# Node_Sensor_Schematic.net
KiCad netlist of a schematic drawn in Altium Designer
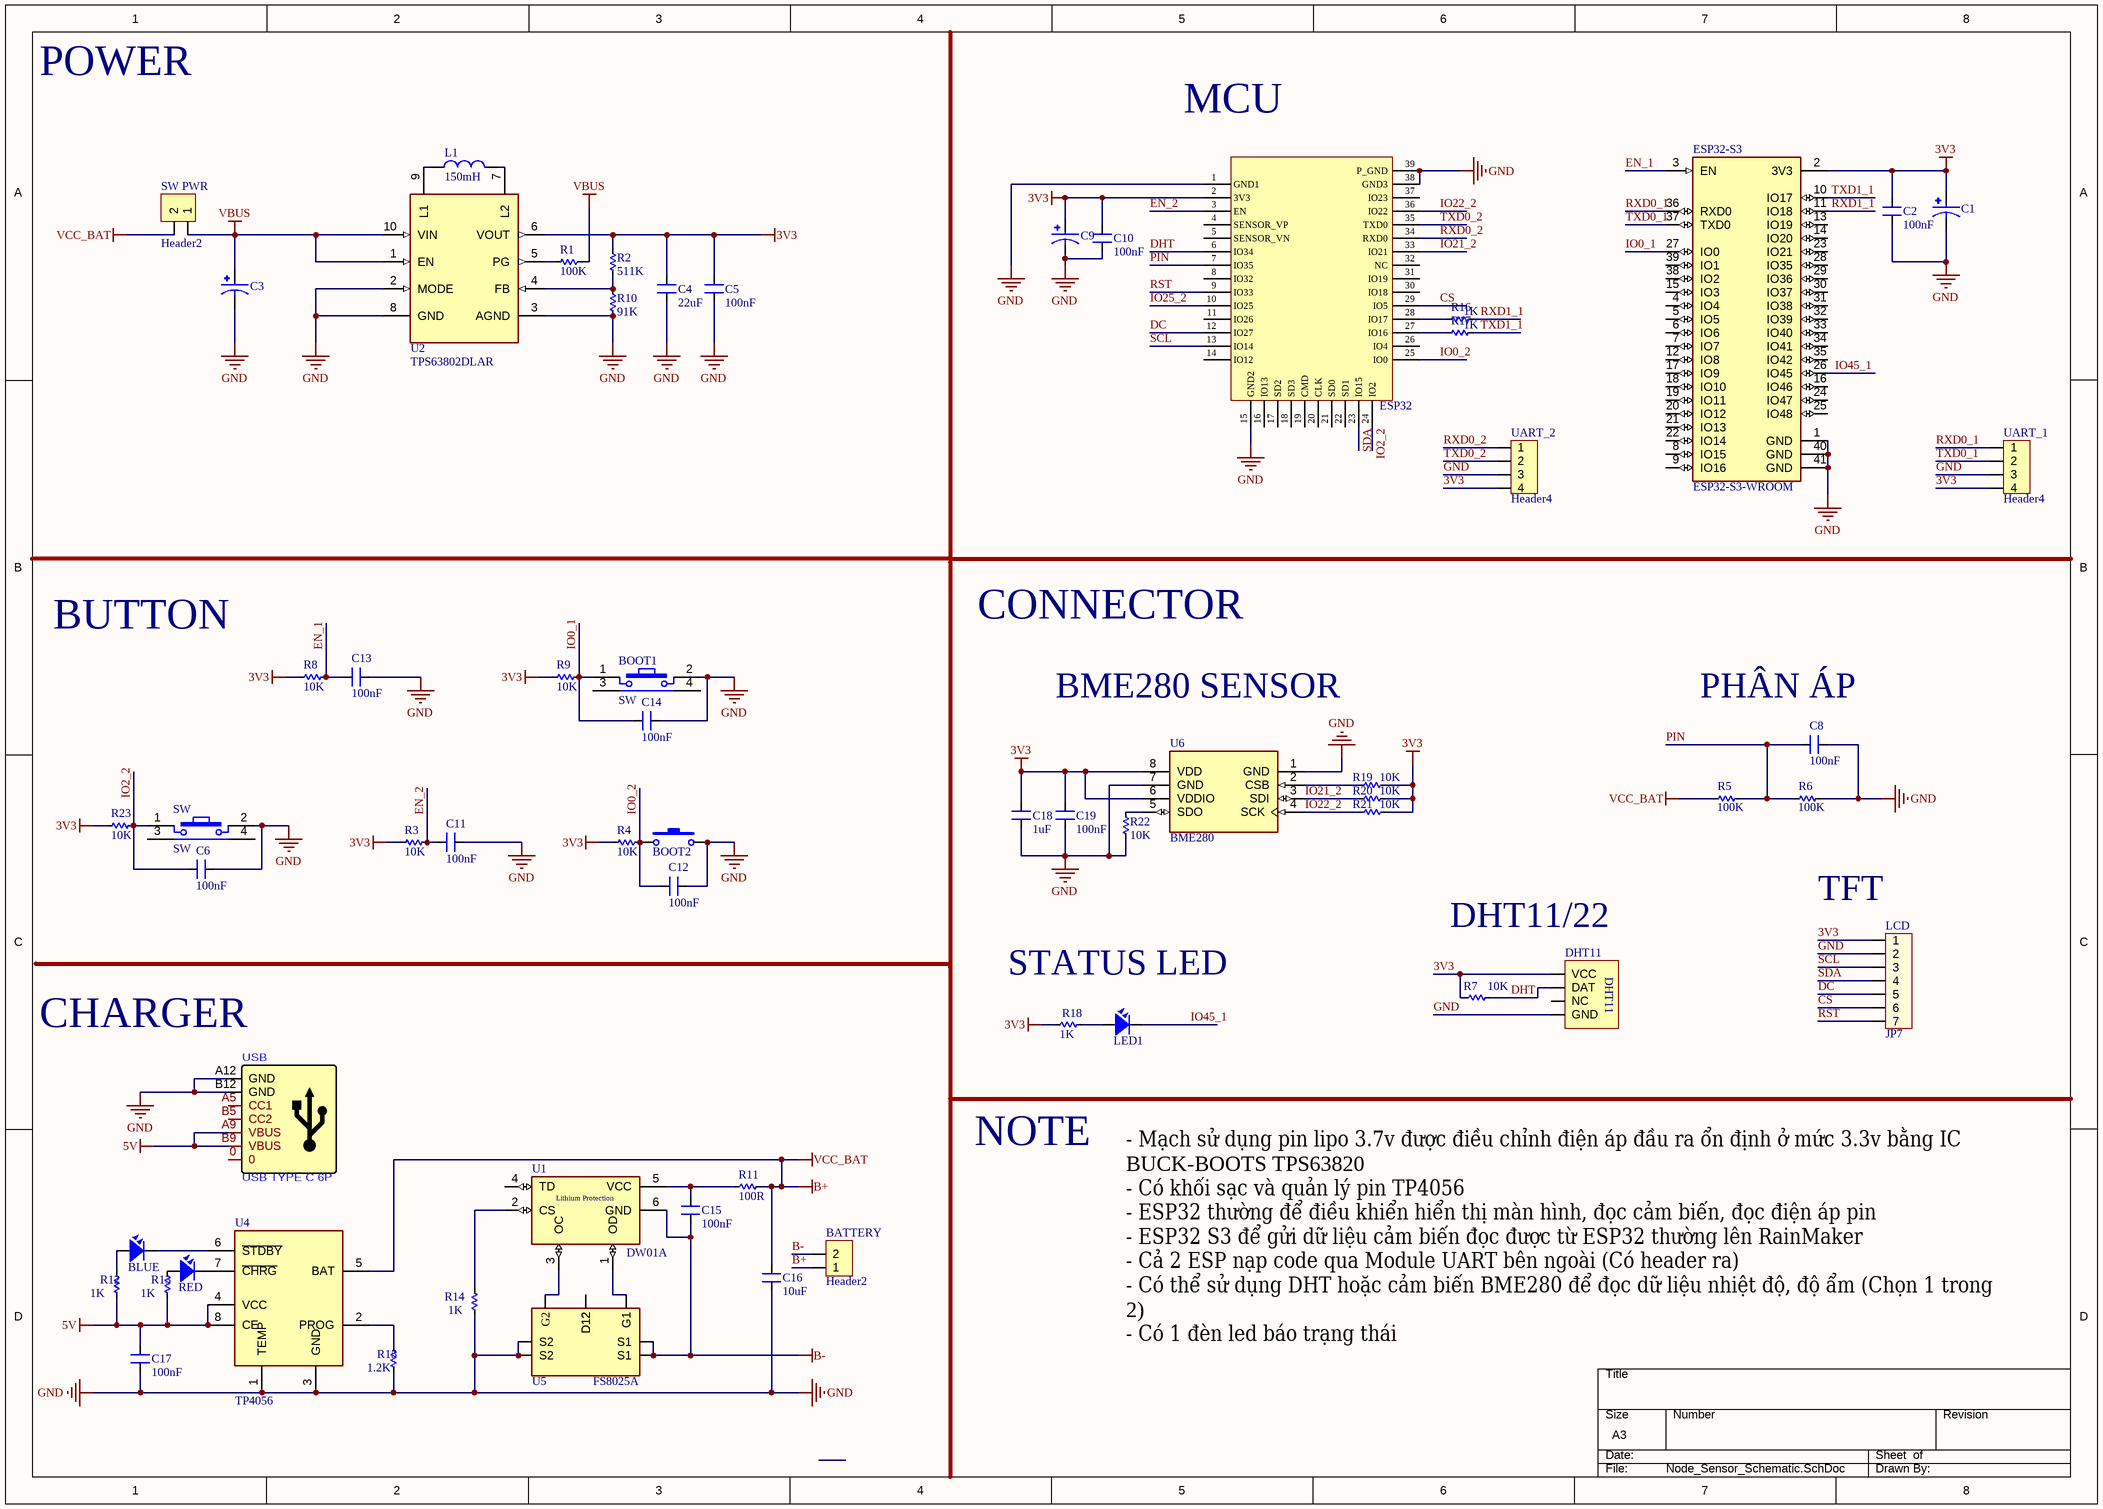
[diagram p0: Node_Sensor_Schematic.SchDoc]

(export (version "E")
  (design (tool "Eeschema 10.0.6"))
  (components
    (comp (ref "BATTERY")
      (value "Header2")
      (footprint "Header2")
      (description "Header IDC, 2 x 1 Pin Vertical 2.54mm Pitch (Non-Boxed, Male)")
      (fields
        (field (name "MANUFACTURER") "Würth Elektronik eiSos GmbH")
        (field (name "PARTNO") "613002143121")
        (field (name "CREATED BY") "Karrer Zheng")
      )
      (libsource (lib "My Library") (part "Header2"))
    )
    (comp (ref "BLUE")
      (value "LED")
      (footprint "My Library:LED-0603")
      (libsource (lib "My Library") (part "LED SMD"))
    )
    (comp (ref "BOOT1")
      (value "SW")
      (footprint "TACTILE SWITCH TC-0203")
      (description "Switch button 4 pin")
      (libsource (lib "Altium_Devzone") (part "SW4-DIP"))
    )
    (comp (ref "BOOT2")
      (value "SW-SMD")
      (footprint "SW_B3U-1000P")
      (description "Switch")
      (fields (field (name "PUBLISHER") "Altium Limited"))
      (libsource (lib "My Library") (part "SW-SMD"))
    )
    (comp (ref "C1")
      (value "CAP_TANTALUM_SMD")
      (footprint "CAP_TANTALUM_3216")
      (description "Capacitor, Tantalum")
      (fields (field (name "MF") "AVX") (field (name "MP") "TAJB475K025RNJ"))
      (libsource (lib "My Library") (part "CAP_TANTALUM_SMD"))
    )
    (comp (ref "C2")
      (value "100nF")
      (footprint "C-0603")
      (description "Cap SMD")
      (libsource (lib "My Library") (part "CM"))
    )
    (comp (ref "C3")
      (value "10uF/16V")
      (footprint "CAP_TANTALUM_3216")
      (description "Capacitor, Tantalum")
      (fields (field (name "MF") "AVX") (field (name "MP") "TAJB475K025RNJ"))
      (libsource (lib "My Library") (part "CAP_TANTALUM_SMD"))
    )
    (comp (ref "C4")
      (value "22uF")
      (footprint "SM-0805")
      (description "Cap SMD")
      (libsource (lib "My Library") (part "CM"))
    )
    (comp (ref "C5")
      (value "100nF")
      (footprint "SM-0805")
      (description "Cap SMD")
      (libsource (lib "My Library") (part "CM"))
    )
    (comp (ref "C6")
      (value "100nF")
      (footprint "C-0603")
      (description "Cap SMD")
      (libsource (lib "My Library") (part "CM"))
    )
    (comp (ref "C8")
      (value "100nF")
      (footprint "C-0603")
      (description "Cap SMD")
      (libsource (lib "My Library") (part "CM"))
    )
    (comp (ref "C9")
      (value "CAP_TANTALUM_SMD")
      (footprint "CAP_TANTALUM_3216")
      (description "Capacitor, Tantalum")
      (fields (field (name "MF") "AVX") (field (name "MP") "TAJB475K025RNJ"))
      (libsource (lib "My Library") (part "CAP_TANTALUM_SMD"))
    )
    (comp (ref "C10")
      (value "100nF")
      (footprint "C-0603")
      (description "Cap SMD")
      (libsource (lib "My Library") (part "CM"))
    )
    (comp (ref "C11")
      (value "100nF")
      (footprint "C-0603")
      (description "Cap SMD")
      (libsource (lib "My Library") (part "CM"))
    )
    (comp (ref "C12")
      (value "100nF")
      (footprint "C-0603")
      (description "Cap SMD")
      (libsource (lib "My Library") (part "CM"))
    )
    (comp (ref "C13")
      (value "100nF")
      (footprint "C-0603")
      (description "Cap SMD")
      (libsource (lib "My Library") (part "CM"))
    )
    (comp (ref "C14")
      (value "100nF")
      (footprint "C-0603")
      (description "Cap SMD")
      (libsource (lib "My Library") (part "CM"))
    )
    (comp (ref "C15")
      (value "100nF")
      (footprint "C-0603")
      (description "Cap SMD")
      (libsource (lib "My Library") (part "CM"))
    )
    (comp (ref "C16")
      (value "10uF")
      (footprint "SM-0805")
      (description "Cap SMD")
      (libsource (lib "My Library") (part "CM"))
    )
    (comp (ref "C17")
      (value "100nF")
      (footprint "C-0603")
      (description "Cap SMD")
      (libsource (lib "My Library") (part "CM"))
    )
    (comp (ref "C18")
      (value "1uF")
      (footprint "C-0603")
      (description "Cap SMD")
      (libsource (lib "My Library") (part "CM"))
    )
    (comp (ref "C19")
      (value "100nF")
      (footprint "C-0603")
      (description "Cap SMD")
      (libsource (lib "My Library") (part "CM"))
    )
    (comp (ref "DHT11")
      (value "DHT11")
      (footprint "DHT11")
      (fields
        (field (name "MANUFACTURER") "Würth Elektronik eiSos GmbH")
        (field (name "PARTNO") "613004143121")
        (field (name "CREATED BY") "Karrer Zheng")
      )
      (libsource (lib "My Library") (part "DHT11"))
    )
    (comp (ref "ESP32")
      (value "ESP32")
      (footprint "ESP32-WROOM-32U")
      (libsource (lib "My Library") (part "ESP-WROOM-32"))
    )
    (comp (ref "ESP32-S3")
      (value "ESP32-S3-WROOM")
      (footprint "ESP32-S3-WROOM-1")
      (fields
        (field (name "MF") "{'manufacturer': u'Espressif Systems'}")
        (field (name "MP") "ESP32-S3-WROOM-1-N8")
      )
      (libsource (lib "My Library") (part "ESP32-S3-WROOM"))
    )
    (comp (ref "L1")
      (value "150mH")
      (footprint "INDUCTOR_SMD_4X4MM")
      (description "Inductor")
      (libsource (lib "My Library") (part "Inductor_SMD"))
    )
    (comp (ref "LCD")
      (value "JP7")
      (footprint "653007114822")
      (description "Connector 7")
      (libsource (lib "Altium_Devzone") (part "Header7"))
    )
    (comp (ref "LED1")
      (value "LED")
      (footprint "My Library:LED-0603")
      (libsource (lib "My Library") (part "LED SMD"))
    )
    (comp (ref "R1")
      (value "100K")
      (footprint "RES-SMD-0603")
      (description "Resistor")
      (fields
        (field (name "MANUFACTURER") "Generic Components")
        (field (name "PUBLISHER") "Altium Hobart Technology Centre")
      )
      (libsource (lib "My Library") (part "Res-SMD"))
    )
    (comp (ref "R2")
      (value "511K")
      (footprint "RES-SMD-0603")
      (description "Resistor")
      (fields
        (field (name "MANUFACTURER") "Generic Components")
        (field (name "PUBLISHER") "Altium Hobart Technology Centre")
      )
      (libsource (lib "My Library") (part "Res-SMD"))
    )
    (comp (ref "R3")
      (value "10K")
      (footprint "RES-SMD-0603")
      (description "Resistor")
      (fields
        (field (name "MANUFACTURER") "Generic Components")
        (field (name "PUBLISHER") "Altium Hobart Technology Centre")
      )
      (libsource (lib "My Library") (part "Res-SMD"))
    )
    (comp (ref "R4")
      (value "10K")
      (footprint "RES-SMD-0603")
      (description "Resistor")
      (fields
        (field (name "MANUFACTURER") "Generic Components")
        (field (name "PUBLISHER") "Altium Hobart Technology Centre")
      )
      (libsource (lib "My Library") (part "Res-SMD"))
    )
    (comp (ref "R5")
      (value "100K")
      (footprint "RES-SMD-0603")
      (description "Resistor")
      (fields
        (field (name "MANUFACTURER") "Generic Components")
        (field (name "PUBLISHER") "Altium Hobart Technology Centre")
      )
      (libsource (lib "My Library") (part "Res-SMD"))
    )
    (comp (ref "R6")
      (value "100K")
      (footprint "RES-SMD-0603")
      (description "Resistor")
      (fields
        (field (name "MANUFACTURER") "Generic Components")
        (field (name "PUBLISHER") "Altium Hobart Technology Centre")
      )
      (libsource (lib "My Library") (part "Res-SMD"))
    )
    (comp (ref "R7")
      (value "10K")
      (footprint "RES-SMD-0603")
      (description "Resistor")
      (fields
        (field (name "MANUFACTURER") "Generic Components")
        (field (name "PUBLISHER") "Altium Hobart Technology Centre")
      )
      (libsource (lib "My Library") (part "Res-SMD"))
    )
    (comp (ref "R8")
      (value "10K")
      (footprint "RES-SMD-0603")
      (description "Resistor")
      (fields
        (field (name "MANUFACTURER") "Generic Components")
        (field (name "PUBLISHER") "Altium Hobart Technology Centre")
      )
      (libsource (lib "My Library") (part "Res-SMD"))
    )
    (comp (ref "R9")
      (value "10K")
      (footprint "RES-SMD-0603")
      (description "Resistor")
      (fields
        (field (name "MANUFACTURER") "Generic Components")
        (field (name "PUBLISHER") "Altium Hobart Technology Centre")
      )
      (libsource (lib "My Library") (part "Res-SMD"))
    )
    (comp (ref "R10")
      (value "91K")
      (footprint "RES-SMD-0603")
      (description "Resistor")
      (fields
        (field (name "MANUFACTURER") "Generic Components")
        (field (name "PUBLISHER") "Altium Hobart Technology Centre")
      )
      (libsource (lib "My Library") (part "Res-SMD"))
    )
    (comp (ref "R11")
      (value "100R")
      (footprint "RES-SMD-0603")
      (description "Resistor")
      (fields
        (field (name "MANUFACTURER") "Generic Components")
        (field (name "PUBLISHER") "Altium Hobart Technology Centre")
      )
      (libsource (lib "My Library") (part "Res-SMD"))
    )
    (comp (ref "R12")
      (value "1K")
      (footprint "RES-SMD-0603")
      (description "Resistor")
      (fields
        (field (name "MANUFACTURER") "Generic Components")
        (field (name "PUBLISHER") "Altium Hobart Technology Centre")
      )
      (libsource (lib "My Library") (part "Res-SMD"))
    )
    (comp (ref "R13")
      (value "1K")
      (footprint "RES-SMD-0603")
      (description "Resistor")
      (fields
        (field (name "MANUFACTURER") "Generic Components")
        (field (name "PUBLISHER") "Altium Hobart Technology Centre")
      )
      (libsource (lib "My Library") (part "Res-SMD"))
    )
    (comp (ref "R14")
      (value "1K")
      (footprint "RES-SMD-0603")
      (description "Resistor")
      (fields
        (field (name "MANUFACTURER") "Generic Components")
        (field (name "PUBLISHER") "Altium Hobart Technology Centre")
      )
      (libsource (lib "My Library") (part "Res-SMD"))
    )
    (comp (ref "R15")
      (value "1.2K")
      (footprint "RES-SMD-0603")
      (description "Resistor")
      (fields
        (field (name "MANUFACTURER") "Generic Components")
        (field (name "PUBLISHER") "Altium Hobart Technology Centre")
      )
      (libsource (lib "My Library") (part "Res-SMD"))
    )
    (comp (ref "R16")
      (value "1K")
      (footprint "RES-SMD-0603")
      (description "Resistor")
      (fields
        (field (name "MANUFACTURER") "Generic Components")
        (field (name "PUBLISHER") "Altium Hobart Technology Centre")
      )
      (libsource (lib "My Library") (part "Res-SMD"))
    )
    (comp (ref "R17")
      (value "1K")
      (footprint "RES-SMD-0603")
      (description "Resistor")
      (fields
        (field (name "MANUFACTURER") "Generic Components")
        (field (name "PUBLISHER") "Altium Hobart Technology Centre")
      )
      (libsource (lib "My Library") (part "Res-SMD"))
    )
    (comp (ref "R18")
      (value "1K")
      (footprint "RES-SMD-0603")
      (description "Resistor")
      (fields
        (field (name "MANUFACTURER") "Generic Components")
        (field (name "PUBLISHER") "Altium Hobart Technology Centre")
      )
      (libsource (lib "My Library") (part "Res-SMD"))
    )
    (comp (ref "R19")
      (value "10K")
      (footprint "RES-SMD-0603")
      (description "Resistor")
      (fields
        (field (name "MANUFACTURER") "Generic Components")
        (field (name "PUBLISHER") "Altium Hobart Technology Centre")
      )
      (libsource (lib "My Library") (part "Res-SMD"))
    )
    (comp (ref "R20")
      (value "10K")
      (footprint "RES-SMD-0603")
      (description "Resistor")
      (fields
        (field (name "MANUFACTURER") "Generic Components")
        (field (name "PUBLISHER") "Altium Hobart Technology Centre")
      )
      (libsource (lib "My Library") (part "Res-SMD"))
    )
    (comp (ref "R21")
      (value "10K")
      (footprint "RES-SMD-0603")
      (description "Resistor")
      (fields
        (field (name "MANUFACTURER") "Generic Components")
        (field (name "PUBLISHER") "Altium Hobart Technology Centre")
      )
      (libsource (lib "My Library") (part "Res-SMD"))
    )
    (comp (ref "R22")
      (value "10K")
      (footprint "RES-SMD-0603")
      (description "Resistor")
      (fields
        (field (name "MANUFACTURER") "Generic Components")
        (field (name "PUBLISHER") "Altium Hobart Technology Centre")
      )
      (libsource (lib "My Library") (part "Res-SMD"))
    )
    (comp (ref "R23")
      (value "10K")
      (footprint "RES-SMD-0603")
      (description "Resistor")
      (fields
        (field (name "MANUFACTURER") "Generic Components")
        (field (name "PUBLISHER") "Altium Hobart Technology Centre")
      )
      (libsource (lib "My Library") (part "Res-SMD"))
    )
    (comp (ref "RED")
      (value "LED")
      (footprint "My Library:LED-0603")
      (libsource (lib "My Library") (part "LED SMD"))
    )
    (comp (ref "SW")
      (value "SW")
      (footprint "TACTILE SWITCH TC-0203")
      (description "Switch button 4 pin")
      (libsource (lib "Altium_Devzone") (part "SW4-DIP"))
    )
    (comp (ref "SW PWR")
      (value "Header2")
      (footprint "Header2")
      (description "Header IDC, 2 x 1 Pin Vertical 2.54mm Pitch (Non-Boxed, Male)")
      (fields
        (field (name "MANUFACTURER") "Würth Elektronik eiSos GmbH")
        (field (name "PARTNO") "613002143121")
        (field (name "CREATED BY") "Karrer Zheng")
      )
      (libsource (lib "") (part "Header2_1"))
    )
    (comp (ref "U1")
      (value "DW01A")
      (footprint "My Library:SOT23-6")
      (description "One Cell Lithium-ion/Polymer Battery Protection IC")
      (fields (field (name "MF") "Fortune Semiconductor"))
      (libsource (lib "My Library") (part "DW01A"))
    )
    (comp (ref "U2")
      (value "TPS63802DLAR")
      (footprint "TPS63802DLAR")
      (description "2-A, high-efficient, 11-ÂµA quiescent current buck-boost converter in QFN/DFN package")
      (fields (field (name "MF") "Texas Instruments"))
      (libsource (lib "My Library") (part "TPS63802DLAR"))
    )
    (comp (ref "U4")
      (value "TP4056")
      (footprint "SOP127P600X175-9N")
      (description "Complete single cell Li-Ion battery with a constant current / constant voltage linear charger")
      (fields (field (name "MF") "NanJing Top Power ASIC Corp."))
      (libsource (lib "My Library") (part "TP4056"))
    )
    (comp (ref "U5")
      (value "FS8025A")
      (footprint "My Library:TSSOP-8")
      (description "MOSFET N-2CH TSSOP-8")
      (fields (field (name "MP") "M24C64-DFDW6TP"))
      (libsource (lib "My Library") (part "FS8025A"))
    )
    (comp (ref "U6")
      (value "BME280")
      (footprint "BME280 SENSOR")
      (libsource (lib "My Library") (part "BME280"))
    )
    (comp (ref "UART_1")
      (value "Header4")
      (footprint "PAD_4")
      (description "Header IDC, 4 x 1 Pin Vertical 2.54mm Pitch (Non-Boxed, Male)")
      (fields
        (field (name "MANUFACTURER") "Würth Elektronik eiSos GmbH")
        (field (name "PARTNO") "613002143121")
        (field (name "CREATED BY") "Karrer Zheng")
      )
      (libsource (lib "My Library") (part "Header4"))
    )
    (comp (ref "UART_2")
      (value "Header4")
      (footprint "PAD_4")
      (description "Header IDC, 4 x 1 Pin Vertical 2.54mm Pitch (Non-Boxed, Male)")
      (fields
        (field (name "MANUFACTURER") "Würth Elektronik eiSos GmbH")
        (field (name "PARTNO") "613002143121")
        (field (name "CREATED BY") "Karrer Zheng")
      )
      (libsource (lib "My Library") (part "Header4"))
    )
    (comp (ref "USB")
      (value "USB TYPE C 6P")
      (footprint "TYPE-C-SMD_TYPE-C-6P_C9900001460")
      (description "UJC-HP-3-SMT-TR")
      (libsource (lib "Altium_Devzone") (part "USB TYPE C 6P"))
    )
  )
  (nets
    (net (code "2") (name "/CS") (class "Default")
      (node (ref "ESP32") (pin "29") (pinfunction "IO5_29") (pintype "passive"))
      (node (ref "LCD") (pin "6") (pinfunction "6_6") (pintype "passive"))
    )
    (net (code "3") (name "/DC") (class "Default")
      (node (ref "ESP32") (pin "12") (pinfunction "IO27_12") (pintype "passive"))
      (node (ref "LCD") (pin "5") (pinfunction "5_5") (pintype "passive"))
    )
    (net (code "4") (name "/DHT") (class "Default")
      (node (ref "DHT11") (pin "2") (pinfunction "DAT_2") (pintype "passive"))
      (node (ref "ESP32") (pin "6") (pinfunction "IO34_6") (pintype "passive"))
      (node (ref "R7") (pin "2") (pinfunction "2_2") (pintype "passive"))
    )
    (net (code "5") (name "/EN_1") (class "Default")
      (node (ref "C13") (pin "2") (pinfunction "2_2") (pintype "passive"))
      (node (ref "ESP32-S3") (pin "3") (pinfunction "EN_3") (pintype "input"))
      (node (ref "R8") (pin "1") (pinfunction "1_1") (pintype "passive"))
    )
    (net (code "6") (name "/EN_2") (class "Default")
      (node (ref "C11") (pin "2") (pinfunction "2_2") (pintype "passive"))
      (node (ref "ESP32") (pin "3") (pinfunction "EN_3") (pintype "passive"))
      (node (ref "R3") (pin "1") (pinfunction "1_1") (pintype "passive"))
    )
    (net (code "7") (name "/IO0_1") (class "Default")
      (node (ref "BOOT1") (pin "1") (pintype "passive"))
      (node (ref "C14") (pin "2") (pinfunction "2_2") (pintype "passive"))
      (node (ref "ESP32-S3") (pin "27") (pinfunction "IO0_27") (pintype "bidirectional"))
      (node (ref "R9") (pin "1") (pinfunction "1_1") (pintype "passive"))
    )
    (net (code "8") (name "/IO0_2") (class "Default")
      (node (ref "BOOT2") (pin "1") (pinfunction "1_1") (pintype "passive"))
      (node (ref "C12") (pin "2") (pinfunction "2_2") (pintype "passive"))
      (node (ref "ESP32") (pin "25") (pinfunction "IO0_25") (pintype "passive"))
      (node (ref "R4") (pin "1") (pinfunction "1_1") (pintype "passive"))
    )
    (net (code "9") (name "/IO2_2") (class "Default")
      (node (ref "C6") (pin "2") (pinfunction "2_2") (pintype "passive"))
      (node (ref "ESP32") (pin "24") (pinfunction "IO2_24") (pintype "passive"))
      (node (ref "R23") (pin "1") (pinfunction "1_1") (pintype "passive"))
      (node (ref "SW") (pin "1") (pintype "passive"))
    )
    (net (code "10") (name "/IO21_2") (class "Default")
      (node (ref "ESP32") (pin "33") (pinfunction "IO21_33") (pintype "passive"))
      (node (ref "R20") (pin "2") (pinfunction "2_2") (pintype "passive"))
      (node (ref "U6") (pin "3") (pinfunction "SDI_3") (pintype "bidirectional"))
    )
    (net (code "11") (name "/IO22_2") (class "Default")
      (node (ref "ESP32") (pin "36") (pinfunction "IO22_36") (pintype "passive"))
      (node (ref "R21") (pin "2") (pinfunction "2_2") (pintype "passive"))
      (node (ref "U6") (pin "4") (pinfunction "SCK_4") (pintype "input"))
    )
    (net (code "12") (name "/IO25_2") (class "Default")
      (node (ref "ESP32") (pin "10") (pinfunction "IO25_10") (pintype "passive"))
    )
    (net (code "13") (name "/IO45_1") (class "Default")
      (node (ref "ESP32-S3") (pin "26") (pinfunction "IO45_26") (pintype "bidirectional"))
      (node (ref "LED1") (pin "2") (pinfunction "2_2") (pintype "passive"))
    )
    (net (code "14") (name "/PIN") (class "Default")
      (node (ref "C8") (pin "2") (pinfunction "2_2") (pintype "passive"))
      (node (ref "ESP32") (pin "7") (pinfunction "IO35_7") (pintype "passive"))
      (node (ref "R5") (pin "2") (pinfunction "2_2") (pintype "passive"))
      (node (ref "R6") (pin "1") (pinfunction "1_1") (pintype "passive"))
    )
    (net (code "15") (name "/RST") (class "Default")
      (node (ref "ESP32") (pin "9") (pinfunction "IO33_9") (pintype "passive"))
      (node (ref "LCD") (pin "7") (pinfunction "7_7") (pintype "passive"))
    )
    (net (code "16") (name "/RXD0_1") (class "Default")
      (node (ref "ESP32-S3") (pin "36") (pinfunction "RXD0_36") (pintype "bidirectional"))
      (node (ref "UART_1") (pin "1") (pinfunction "1_1") (pintype "passive"))
    )
    (net (code "17") (name "/RXD0_2") (class "Default")
      (node (ref "ESP32") (pin "34") (pinfunction "RXD0_34") (pintype "passive"))
      (node (ref "UART_2") (pin "1") (pinfunction "1_1") (pintype "passive"))
    )
    (net (code "18") (name "/RXD1_1") (class "Default")
      (node (ref "ESP32-S3") (pin "11") (pinfunction "IO18_11") (pintype "bidirectional"))
      (node (ref "R16") (pin "1") (pinfunction "1_1") (pintype "passive"))
    )
    (net (code "19") (name "/SCL") (class "Default")
      (node (ref "ESP32") (pin "13") (pinfunction "IO14_13") (pintype "passive"))
      (node (ref "LCD") (pin "3") (pinfunction "3_3") (pintype "passive"))
    )
    (net (code "20") (name "/SDA") (class "Default")
      (node (ref "ESP32") (pin "23") (pinfunction "IO15_23") (pintype "passive"))
      (node (ref "LCD") (pin "4") (pinfunction "4_4") (pintype "passive"))
    )
    (net (code "21") (name "/TXD0_1") (class "Default")
      (node (ref "ESP32-S3") (pin "37") (pinfunction "TXD0_37") (pintype "bidirectional"))
      (node (ref "UART_1") (pin "2") (pinfunction "2_2") (pintype "passive"))
    )
    (net (code "22") (name "/TXD0_2") (class "Default")
      (node (ref "ESP32") (pin "35") (pinfunction "TXD0_35") (pintype "passive"))
      (node (ref "UART_2") (pin "2") (pinfunction "2_2") (pintype "passive"))
    )
    (net (code "23") (name "/TXD1_1") (class "Default")
      (node (ref "ESP32-S3") (pin "10") (pinfunction "IO17_10") (pintype "bidirectional"))
      (node (ref "R17") (pin "1") (pinfunction "1_1") (pintype "passive"))
    )
    (net (code "24") (name "3V3") (class "Default")
      (node (ref "C1") (pin "1") (pinfunction "1_1") (pintype "passive"))
      (node (ref "C10") (pin "2") (pinfunction "2_2") (pintype "passive"))
      (node (ref "C18") (pin "1") (pinfunction "1_1") (pintype "passive"))
      (node (ref "C19") (pin "1") (pinfunction "1_1") (pintype "passive"))
      (node (ref "C2") (pin "2") (pinfunction "2_2") (pintype "passive"))
      (node (ref "C4") (pin "2") (pinfunction "2_2") (pintype "passive"))
      (node (ref "C5") (pin "2") (pinfunction "2_2") (pintype "passive"))
      (node (ref "C9") (pin "1") (pinfunction "1_1") (pintype "passive"))
      (node (ref "DHT11") (pin "1") (pinfunction "VCC_1") (pintype "passive"))
      (node (ref "ESP32") (pin "2") (pinfunction "3V3_2") (pintype "passive"))
      (node (ref "ESP32-S3") (pin "2") (pinfunction "3V3_2") (pintype "power_in"))
      (node (ref "LCD") (pin "1") (pinfunction "1_1") (pintype "passive"))
      (node (ref "R18") (pin "2") (pinfunction "2_2") (pintype "passive"))
      (node (ref "R19") (pin "1") (pinfunction "1_1") (pintype "passive"))
      (node (ref "R2") (pin "1") (pinfunction "1_1") (pintype "passive"))
      (node (ref "R20") (pin "1") (pinfunction "1_1") (pintype "passive"))
      (node (ref "R21") (pin "1") (pinfunction "1_1") (pintype "passive"))
      (node (ref "R23") (pin "2") (pinfunction "2_2") (pintype "passive"))
      (node (ref "R3") (pin "2") (pinfunction "2_2") (pintype "passive"))
      (node (ref "R4") (pin "2") (pinfunction "2_2") (pintype "passive"))
      (node (ref "R7") (pin "1") (pinfunction "1_1") (pintype "passive"))
      (node (ref "R8") (pin "2") (pinfunction "2_2") (pintype "passive"))
      (node (ref "R9") (pin "2") (pinfunction "2_2") (pintype "passive"))
      (node (ref "U2") (pin "6") (pinfunction "VOUT_6") (pintype "output"))
      (node (ref "U6") (pin "6") (pinfunction "VDDIO_6") (pintype "power_in"))
      (node (ref "U6") (pin "8") (pinfunction "VDD_8") (pintype "power_in"))
      (node (ref "UART_1") (pin "4") (pinfunction "4_4") (pintype "passive"))
      (node (ref "UART_2") (pin "4") (pinfunction "4_4") (pintype "passive"))
    )
    (net (code "25") (name "5V") (class "Default")
      (node (ref "C17") (pin "2") (pinfunction "2_2") (pintype "passive"))
      (node (ref "R12") (pin "2") (pinfunction "2_2") (pintype "passive"))
      (node (ref "R13") (pin "2") (pinfunction "2_2") (pintype "passive"))
      (node (ref "U4") (pin "4") (pinfunction "VCC_4") (pintype "power_in"))
      (node (ref "U4") (pin "8") (pinfunction "CE_8") (pintype "power_in"))
      (node (ref "USB") (pin "A9") (pinfunction "VBUS_A9") (pintype "passive"))
      (node (ref "USB") (pin "B9") (pinfunction "VBUS_B9") (pintype "passive"))
    )
    (net (code "26") (name "B+") (class "Default")
      (node (ref "BATTERY") (pin "1") (pinfunction "1_1") (pintype "passive"))
      (node (ref "C16") (pin "2") (pinfunction "2_2") (pintype "passive"))
      (node (ref "R11") (pin "2") (pinfunction "2_2") (pintype "passive"))
      (node (ref "R5") (pin "1") (pinfunction "1_1") (pintype "passive"))
      (node (ref "SW PWR") (pin "2") (pinfunction "2_2") (pintype "passive"))
      (node (ref "U4") (pin "5") (pinfunction "BAT_5") (pintype "passive"))
    )
    (net (code "27") (name "B-") (class "Default")
      (node (ref "BATTERY") (pin "2") (pinfunction "2_2") (pintype "passive"))
      (node (ref "C15") (pin "1") (pinfunction "1_1") (pintype "passive"))
      (node (ref "U1") (pin "6") (pinfunction "GND_6") (pintype "power_in"))
      (node (ref "U5") (pin "2") (pinfunction "S1_2") (pintype "passive"))
      (node (ref "U5") (pin "3") (pinfunction "S1_3") (pintype "passive"))
    )
    (net (code "28") (name "GND") (class "Default")
      (node (ref "BOOT1") (pin "2") (pintype "passive"))
      (node (ref "BOOT2") (pin "2") (pinfunction "2_2") (pintype "passive"))
      (node (ref "C1") (pin "2") (pinfunction "2_2") (pintype "passive"))
      (node (ref "C10") (pin "1") (pinfunction "1_1") (pintype "passive"))
      (node (ref "C11") (pin "1") (pinfunction "1_1") (pintype "passive"))
      (node (ref "C12") (pin "1") (pinfunction "1_1") (pintype "passive"))
      (node (ref "C13") (pin "1") (pinfunction "1_1") (pintype "passive"))
      (node (ref "C14") (pin "1") (pinfunction "1_1") (pintype "passive"))
      (node (ref "C16") (pin "1") (pinfunction "1_1") (pintype "passive"))
      (node (ref "C17") (pin "1") (pinfunction "1_1") (pintype "passive"))
      (node (ref "C18") (pin "2") (pinfunction "2_2") (pintype "passive"))
      (node (ref "C19") (pin "2") (pinfunction "2_2") (pintype "passive"))
      (node (ref "C2") (pin "1") (pinfunction "1_1") (pintype "passive"))
      (node (ref "C3") (pin "2") (pinfunction "2_2") (pintype "passive"))
      (node (ref "C4") (pin "1") (pinfunction "1_1") (pintype "passive"))
      (node (ref "C5") (pin "1") (pinfunction "1_1") (pintype "passive"))
      (node (ref "C6") (pin "1") (pinfunction "1_1") (pintype "passive"))
      (node (ref "C8") (pin "1") (pinfunction "1_1") (pintype "passive"))
      (node (ref "C9") (pin "2") (pinfunction "2_2") (pintype "passive"))
      (node (ref "DHT11") (pin "4") (pinfunction "GND_4") (pintype "passive"))
      (node (ref "ESP32") (pin "1") (pinfunction "GND1_1") (pintype "passive"))
      (node (ref "ESP32") (pin "15") (pinfunction "GND2_15") (pintype "passive"))
      (node (ref "ESP32") (pin "38") (pinfunction "GND3_38") (pintype "passive"))
      (node (ref "ESP32") (pin "39") (pinfunction "P_GND_39") (pintype "passive"))
      (node (ref "ESP32-S3") (pin "1") (pinfunction "GND_1") (pintype "power_in"))
      (node (ref "ESP32-S3") (pin "40") (pinfunction "GND_40") (pintype "power_in"))
      (node (ref "ESP32-S3") (pin "41") (pinfunction "GND_41") (pintype "power_in"))
      (node (ref "LCD") (pin "2") (pinfunction "2_2") (pintype "passive"))
      (node (ref "R10") (pin "2") (pinfunction "2_2") (pintype "passive"))
      (node (ref "R14") (pin "2") (pinfunction "2_2") (pintype "passive"))
      (node (ref "R15") (pin "2") (pinfunction "2_2") (pintype "passive"))
      (node (ref "R22") (pin "1") (pinfunction "1_1") (pintype "passive"))
      (node (ref "R6") (pin "2") (pinfunction "2_2") (pintype "passive"))
      (node (ref "SW") (pin "2") (pintype "passive"))
      (node (ref "U2") (pin "2") (pinfunction "MODE_2") (pintype "input"))
      (node (ref "U2") (pin "3") (pinfunction "AGND_3") (pintype "power_in"))
      (node (ref "U2") (pin "8") (pinfunction "GND_8") (pintype "power_in"))
      (node (ref "U4") (pin "1") (pinfunction "TEMP_1") (pintype "power_in"))
      (node (ref "U4") (pin "3") (pinfunction "GND_3") (pintype "power_in"))
      (node (ref "U5") (pin "6") (pinfunction "S2_6") (pintype "passive"))
      (node (ref "U5") (pin "7") (pinfunction "S2_7") (pintype "passive"))
      (node (ref "U6") (pin "1") (pinfunction "GND_1") (pintype "power_in"))
      (node (ref "U6") (pin "7") (pinfunction "GND_7") (pintype "power_in"))
      (node (ref "UART_1") (pin "3") (pinfunction "3_3") (pintype "passive"))
      (node (ref "UART_2") (pin "3") (pinfunction "3_3") (pintype "passive"))
      (node (ref "USB") (pin "A12") (pinfunction "GND_A12") (pintype "passive"))
      (node (ref "USB") (pin "B12") (pinfunction "GND_B12") (pintype "passive"))
    )
    (net (code "29") (name "Net-(BLUE-Pad1)") (class "Default")
      (node (ref "BLUE") (pin "1") (pinfunction "1_1") (pintype "passive"))
      (node (ref "R12") (pin "1") (pinfunction "1_1") (pintype "passive"))
    )
    (net (code "30") (name "Net-(ESP32-IO16)") (class "Default")
      (node (ref "ESP32") (pin "27") (pinfunction "IO16_27") (pintype "passive"))
      (node (ref "R17") (pin "2") (pinfunction "2_2") (pintype "passive"))
    )
    (net (code "31") (name "Net-(ESP32-IO17)") (class "Default")
      (node (ref "ESP32") (pin "28") (pinfunction "IO17_28") (pintype "passive"))
      (node (ref "R16") (pin "2") (pinfunction "2_2") (pintype "passive"))
    )
    (net (code "32") (name "Net-(LED1-Pad1)") (class "Default")
      (node (ref "LED1") (pin "1") (pinfunction "1_1") (pintype "passive"))
      (node (ref "R18") (pin "1") (pinfunction "1_1") (pintype "passive"))
    )
    (net (code "33") (name "Net-(R13-Pad1)") (class "Default")
      (node (ref "R13") (pin "1") (pinfunction "1_1") (pintype "passive"))
      (node (ref "RED") (pin "1") (pinfunction "1_1") (pintype "passive"))
    )
    (net (code "34") (name "Net-(U1-CS)") (class "Default")
      (node (ref "R14") (pin "1") (pinfunction "1_1") (pintype "passive"))
      (node (ref "U1") (pin "2") (pinfunction "CS_2") (pintype "bidirectional"))
    )
    (net (code "35") (name "Net-(U1-OC)") (class "Default")
      (node (ref "U1") (pin "3") (pinfunction "OC_3") (pintype "bidirectional"))
      (node (ref "U5") (pin "5") (pinfunction "G2_5") (pintype "passive"))
    )
    (net (code "36") (name "Net-(U1-OD)") (class "Default")
      (node (ref "U1") (pin "1") (pinfunction "OD_1") (pintype "bidirectional"))
      (node (ref "U5") (pin "4") (pinfunction "G1_4") (pintype "passive"))
    )
    (net (code "37") (name "Net-(U1-VCC)") (class "Default")
      (node (ref "C15") (pin "2") (pinfunction "2_2") (pintype "passive"))
      (node (ref "R11") (pin "1") (pinfunction "1_1") (pintype "passive"))
      (node (ref "U1") (pin "5") (pinfunction "VCC_5") (pintype "power_in"))
    )
    (net (code "38") (name "Net-(U2-FB)") (class "Default")
      (node (ref "R10") (pin "1") (pinfunction "1_1") (pintype "passive"))
      (node (ref "R2") (pin "2") (pinfunction "2_2") (pintype "passive"))
      (node (ref "U2") (pin "4") (pinfunction "FB_4") (pintype "input"))
    )
    (net (code "39") (name "Net-(U2-L1)") (class "Default")
      (node (ref "L1") (pin "1") (pinfunction "1_1") (pintype "passive"))
      (node (ref "U2") (pin "9") (pinfunction "L1_9") (pintype "passive"))
    )
    (net (code "40") (name "Net-(U2-L2)") (class "Default")
      (node (ref "L1") (pin "2") (pinfunction "2_2") (pintype "passive"))
      (node (ref "U2") (pin "7") (pinfunction "L2_7") (pintype "passive"))
    )
    (net (code "41") (name "Net-(U2-PG)") (class "Default")
      (node (ref "R1") (pin "1") (pinfunction "1_1") (pintype "passive"))
      (node (ref "U2") (pin "5") (pinfunction "PG_5") (pintype "output"))
    )
    (net (code "42") (name "Net-(U4-PROG)") (class "Default")
      (node (ref "R15") (pin "1") (pinfunction "1_1") (pintype "passive"))
      (node (ref "U4") (pin "2") (pinfunction "PROG_2") (pintype "passive"))
    )
    (net (code "43") (name "Net-(U4-~{CHRG})") (class "Default")
      (node (ref "RED") (pin "2") (pinfunction "2_2") (pintype "passive"))
      (node (ref "U4") (pin "7") (pinfunction "~{CHRG}_7") (pintype "passive"))
    )
    (net (code "44") (name "Net-(U4-~{STDBY})") (class "Default")
      (node (ref "BLUE") (pin "2") (pinfunction "2_2") (pintype "passive"))
      (node (ref "U4") (pin "6") (pinfunction "~{STDBY}_6") (pintype "passive"))
    )
    (net (code "45") (name "Net-(U5-D12-Pad1)") (class "Default")
      (node (ref "U5") (pin "1") (pinfunction "D12_1") (pintype "passive"))
      (node (ref "U5") (pin "8") (pinfunction "D12_8") (pintype "passive"))
    )
    (net (code "46") (name "Net-(U6-CSB)") (class "Default")
      (node (ref "R19") (pin "2") (pinfunction "2_2") (pintype "passive"))
      (node (ref "U6") (pin "2") (pinfunction "CSB_2") (pintype "input"))
    )
    (net (code "47") (name "Net-(U6-SDO)") (class "Default")
      (node (ref "R22") (pin "2") (pinfunction "2_2") (pintype "passive"))
      (node (ref "U6") (pin "5") (pinfunction "SDO_5") (pintype "bidirectional"))
    )
    (net (code "48") (name "VBUS") (class "Default")
      (node (ref "C3") (pin "1") (pinfunction "1_1") (pintype "passive"))
      (node (ref "R1") (pin "2") (pinfunction "2_2") (pintype "passive"))
      (node (ref "SW PWR") (pin "1") (pinfunction "1_1") (pintype "passive"))
      (node (ref "U2") (pin "1") (pinfunction "EN_1") (pintype "input"))
      (node (ref "U2") (pin "10") (pinfunction "VIN_10") (pintype "input"))
    )
    (net (code "49") (name "unconnected-(BOOT1-Pad3)") (class "Default")
      (node (ref "BOOT1") (pin "3") (pintype "passive"))
    )
    (net (code "50") (name "unconnected-(BOOT1-Pad4)") (class "Default")
      (node (ref "BOOT1") (pin "4") (pintype "passive"))
    )
    (net (code "51") (name "unconnected-(DHT11-NC-Pad3)") (class "Default")
      (node (ref "DHT11") (pin "3") (pinfunction "NC_3") (pintype "passive"))
    )
    (net (code "52") (name "unconnected-(ESP32-CLK-Pad20)") (class "Default")
      (node (ref "ESP32") (pin "20") (pinfunction "CLK_20") (pintype "passive"))
    )
    (net (code "53") (name "unconnected-(ESP32-CMD-Pad19)") (class "Default")
      (node (ref "ESP32") (pin "19") (pinfunction "CMD_19") (pintype "passive"))
    )
    (net (code "54") (name "unconnected-(ESP32-IO4-Pad26)") (class "Default")
      (node (ref "ESP32") (pin "26") (pinfunction "IO4_26") (pintype "passive"))
    )
    (net (code "55") (name "unconnected-(ESP32-IO12-Pad14)") (class "Default")
      (node (ref "ESP32") (pin "14") (pinfunction "IO12_14") (pintype "passive"))
    )
    (net (code "56") (name "unconnected-(ESP32-IO13-Pad16)") (class "Default")
      (node (ref "ESP32") (pin "16") (pinfunction "IO13_16") (pintype "passive"))
    )
    (net (code "57") (name "unconnected-(ESP32-IO18-Pad30)") (class "Default")
      (node (ref "ESP32") (pin "30") (pinfunction "IO18_30") (pintype "passive"))
    )
    (net (code "58") (name "unconnected-(ESP32-IO19-Pad31)") (class "Default")
      (node (ref "ESP32") (pin "31") (pinfunction "IO19_31") (pintype "passive"))
    )
    (net (code "59") (name "unconnected-(ESP32-IO23-Pad37)") (class "Default")
      (node (ref "ESP32") (pin "37") (pinfunction "IO23_37") (pintype "passive"))
    )
    (net (code "60") (name "unconnected-(ESP32-IO26-Pad11)") (class "Default")
      (node (ref "ESP32") (pin "11") (pinfunction "IO26_11") (pintype "passive"))
    )
    (net (code "61") (name "unconnected-(ESP32-IO32-Pad8)") (class "Default")
      (node (ref "ESP32") (pin "8") (pinfunction "IO32_8") (pintype "passive"))
    )
    (net (code "62") (name "unconnected-(ESP32-NC-Pad32)") (class "Default")
      (node (ref "ESP32") (pin "32") (pinfunction "NC_32") (pintype "passive"))
    )
    (net (code "63") (name "unconnected-(ESP32-S3-IO1-Pad39)") (class "Default")
      (node (ref "ESP32-S3") (pin "39") (pinfunction "IO1_39") (pintype "bidirectional"))
    )
    (net (code "64") (name "unconnected-(ESP32-S3-IO2-Pad38)") (class "Default")
      (node (ref "ESP32-S3") (pin "38") (pinfunction "IO2_38") (pintype "bidirectional"))
    )
    (net (code "65") (name "unconnected-(ESP32-S3-IO3-Pad15)") (class "Default")
      (node (ref "ESP32-S3") (pin "15") (pinfunction "IO3_15") (pintype "bidirectional"))
    )
    (net (code "66") (name "unconnected-(ESP32-S3-IO4-Pad4)") (class "Default")
      (node (ref "ESP32-S3") (pin "4") (pinfunction "IO4_4") (pintype "bidirectional"))
    )
    (net (code "67") (name "unconnected-(ESP32-S3-IO5-Pad5)") (class "Default")
      (node (ref "ESP32-S3") (pin "5") (pinfunction "IO5_5") (pintype "bidirectional"))
    )
    (net (code "68") (name "unconnected-(ESP32-S3-IO6-Pad6)") (class "Default")
      (node (ref "ESP32-S3") (pin "6") (pinfunction "IO6_6") (pintype "bidirectional"))
    )
    (net (code "69") (name "unconnected-(ESP32-S3-IO7-Pad7)") (class "Default")
      (node (ref "ESP32-S3") (pin "7") (pinfunction "IO7_7") (pintype "bidirectional"))
    )
    (net (code "70") (name "unconnected-(ESP32-S3-IO8-Pad12)") (class "Default")
      (node (ref "ESP32-S3") (pin "12") (pinfunction "IO8_12") (pintype "bidirectional"))
    )
    (net (code "71") (name "unconnected-(ESP32-S3-IO9-Pad17)") (class "Default")
      (node (ref "ESP32-S3") (pin "17") (pinfunction "IO9_17") (pintype "bidirectional"))
    )
    (net (code "72") (name "unconnected-(ESP32-S3-IO10-Pad18)") (class "Default")
      (node (ref "ESP32-S3") (pin "18") (pinfunction "IO10_18") (pintype "bidirectional"))
    )
    (net (code "73") (name "unconnected-(ESP32-S3-IO11-Pad19)") (class "Default")
      (node (ref "ESP32-S3") (pin "19") (pinfunction "IO11_19") (pintype "bidirectional"))
    )
    (net (code "74") (name "unconnected-(ESP32-S3-IO12-Pad20)") (class "Default")
      (node (ref "ESP32-S3") (pin "20") (pinfunction "IO12_20") (pintype "bidirectional"))
    )
    (net (code "75") (name "unconnected-(ESP32-S3-IO13-Pad21)") (class "Default")
      (node (ref "ESP32-S3") (pin "21") (pinfunction "IO13_21") (pintype "bidirectional"))
    )
    (net (code "76") (name "unconnected-(ESP32-S3-IO14-Pad22)") (class "Default")
      (node (ref "ESP32-S3") (pin "22") (pinfunction "IO14_22") (pintype "bidirectional"))
    )
    (net (code "77") (name "unconnected-(ESP32-S3-IO15-Pad8)") (class "Default")
      (node (ref "ESP32-S3") (pin "8") (pinfunction "IO15_8") (pintype "bidirectional"))
    )
    (net (code "78") (name "unconnected-(ESP32-S3-IO16-Pad9)") (class "Default")
      (node (ref "ESP32-S3") (pin "9") (pinfunction "IO16_9") (pintype "bidirectional"))
    )
    (net (code "79") (name "unconnected-(ESP32-S3-IO19-Pad13)") (class "Default")
      (node (ref "ESP32-S3") (pin "13") (pinfunction "IO19_13") (pintype "bidirectional"))
    )
    (net (code "80") (name "unconnected-(ESP32-S3-IO20-Pad14)") (class "Default")
      (node (ref "ESP32-S3") (pin "14") (pinfunction "IO20_14") (pintype "bidirectional"))
    )
    (net (code "81") (name "unconnected-(ESP32-S3-IO21-Pad23)") (class "Default")
      (node (ref "ESP32-S3") (pin "23") (pinfunction "IO21_23") (pintype "bidirectional"))
    )
    (net (code "82") (name "unconnected-(ESP32-S3-IO35-Pad28)") (class "Default")
      (node (ref "ESP32-S3") (pin "28") (pinfunction "IO35_28") (pintype "bidirectional"))
    )
    (net (code "83") (name "unconnected-(ESP32-S3-IO36-Pad29)") (class "Default")
      (node (ref "ESP32-S3") (pin "29") (pinfunction "IO36_29") (pintype "bidirectional"))
    )
    (net (code "84") (name "unconnected-(ESP32-S3-IO37-Pad30)") (class "Default")
      (node (ref "ESP32-S3") (pin "30") (pinfunction "IO37_30") (pintype "bidirectional"))
    )
    (net (code "85") (name "unconnected-(ESP32-S3-IO38-Pad31)") (class "Default")
      (node (ref "ESP32-S3") (pin "31") (pinfunction "IO38_31") (pintype "bidirectional"))
    )
    (net (code "86") (name "unconnected-(ESP32-S3-IO39-Pad32)") (class "Default")
      (node (ref "ESP32-S3") (pin "32") (pinfunction "IO39_32") (pintype "bidirectional"))
    )
    (net (code "87") (name "unconnected-(ESP32-S3-IO40-Pad33)") (class "Default")
      (node (ref "ESP32-S3") (pin "33") (pinfunction "IO40_33") (pintype "bidirectional"))
    )
    (net (code "88") (name "unconnected-(ESP32-S3-IO41-Pad34)") (class "Default")
      (node (ref "ESP32-S3") (pin "34") (pinfunction "IO41_34") (pintype "bidirectional"))
    )
    (net (code "89") (name "unconnected-(ESP32-S3-IO42-Pad35)") (class "Default")
      (node (ref "ESP32-S3") (pin "35") (pinfunction "IO42_35") (pintype "bidirectional"))
    )
    (net (code "90") (name "unconnected-(ESP32-S3-IO46-Pad16)") (class "Default")
      (node (ref "ESP32-S3") (pin "16") (pinfunction "IO46_16") (pintype "bidirectional"))
    )
    (net (code "91") (name "unconnected-(ESP32-S3-IO47-Pad24)") (class "Default")
      (node (ref "ESP32-S3") (pin "24") (pinfunction "IO47_24") (pintype "bidirectional"))
    )
    (net (code "92") (name "unconnected-(ESP32-S3-IO48-Pad25)") (class "Default")
      (node (ref "ESP32-S3") (pin "25") (pinfunction "IO48_25") (pintype "bidirectional"))
    )
    (net (code "93") (name "unconnected-(ESP32-SD0-Pad21)") (class "Default")
      (node (ref "ESP32") (pin "21") (pinfunction "SD0_21") (pintype "passive"))
    )
    (net (code "94") (name "unconnected-(ESP32-SD1-Pad22)") (class "Default")
      (node (ref "ESP32") (pin "22") (pinfunction "SD1_22") (pintype "passive"))
    )
    (net (code "95") (name "unconnected-(ESP32-SD2-Pad17)") (class "Default")
      (node (ref "ESP32") (pin "17") (pinfunction "SD2_17") (pintype "passive"))
    )
    (net (code "96") (name "unconnected-(ESP32-SD3-Pad18)") (class "Default")
      (node (ref "ESP32") (pin "18") (pinfunction "SD3_18") (pintype "passive"))
    )
    (net (code "97") (name "unconnected-(ESP32-SENSOR_VN-Pad5)") (class "Default")
      (node (ref "ESP32") (pin "5") (pinfunction "SENSOR_VN_5") (pintype "passive"))
    )
    (net (code "98") (name "unconnected-(ESP32-SENSOR_VP-Pad4)") (class "Default")
      (node (ref "ESP32") (pin "4") (pinfunction "SENSOR_VP_4") (pintype "passive"))
    )
    (net (code "99") (name "unconnected-(SW-Pad3)") (class "Default")
      (node (ref "SW") (pin "3") (pintype "passive"))
    )
    (net (code "100") (name "unconnected-(SW-Pad4)") (class "Default")
      (node (ref "SW") (pin "4") (pintype "passive"))
    )
    (net (code "101") (name "unconnected-(U1-TD-Pad4)") (class "Default")
      (node (ref "U1") (pin "4") (pinfunction "TD_4") (pintype "bidirectional"))
    )
    (net (code "102") (name "unconnected-(USB-CC1-PadA5)") (class "Default")
      (node (ref "USB") (pin "A5") (pinfunction "CC1_A5") (pintype "passive"))
    )
    (net (code "103") (name "unconnected-(USB-CC2-PadB5)") (class "Default")
      (node (ref "USB") (pin "B5") (pinfunction "CC2_B5") (pintype "passive"))
    )
    (net (code "104") (name "unconnected-(USB-Pad0)") (class "Default")
      (node (ref "USB") (pin "0") (pinfunction "0_0") (pintype "passive"))
    )
  )
)
